# SimpleTrigger.net
KiCad netlist of a schematic drawn in EAGLE
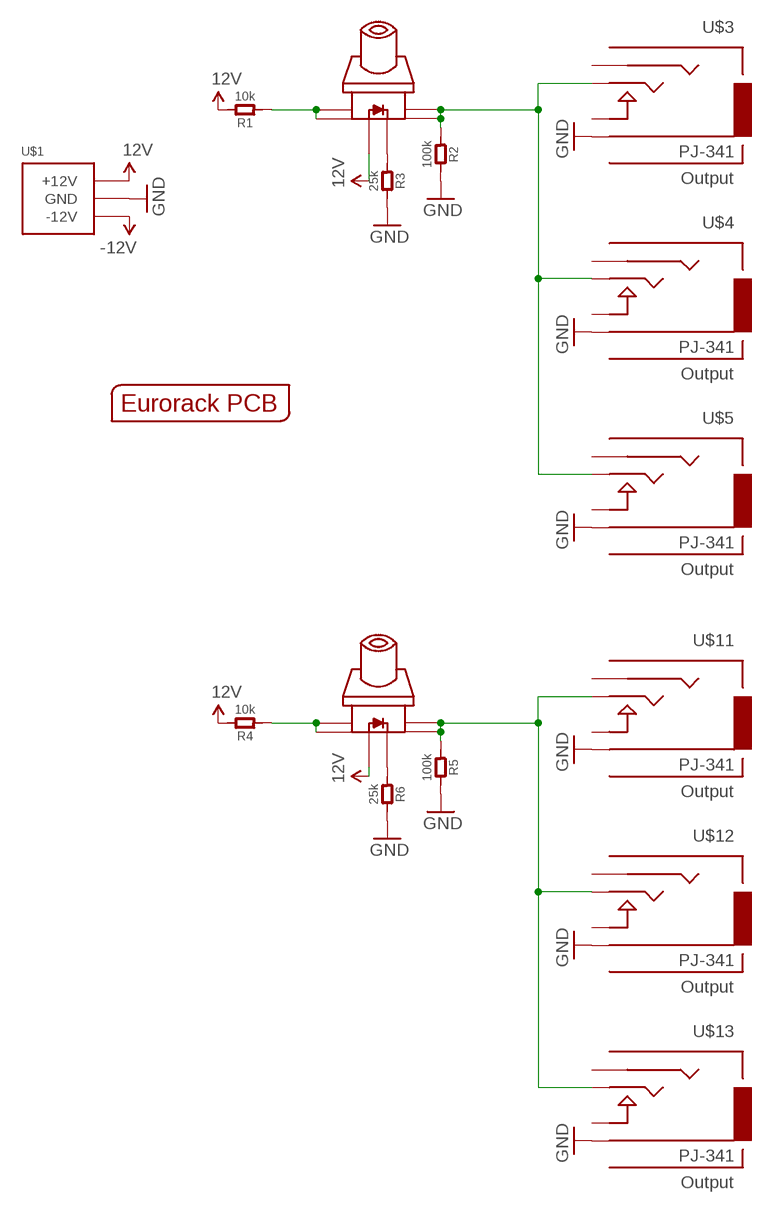
[diagram p0: schematic, sheet 1]

(export (version "E")
  (design (tool "Eeschema 10.0.6"))
  (components
    (comp (ref "R1")
      (value "10k")
      (footprint "eagle-import:R0603")
      (libsource (lib "eagle-import") (part "R-0603"))
    )
    (comp (ref "R2")
      (value "100k")
      (footprint "eagle-import:R0603")
      (libsource (lib "eagle-import") (part "R-0603"))
    )
    (comp (ref "R3")
      (value "25k")
      (footprint "eagle-import:R0603")
      (libsource (lib "eagle-import") (part "R-0603"))
    )
    (comp (ref "R4")
      (value "10k")
      (footprint "eagle-import:R0603")
      (libsource (lib "eagle-import") (part "R-0603"))
    )
    (comp (ref "R5")
      (value "100k")
      (footprint "eagle-import:R0603")
      (libsource (lib "eagle-import") (part "R-0603"))
    )
    (comp (ref "R6")
      (value "25k")
      (footprint "eagle-import:R0603")
      (libsource (lib "eagle-import") (part "R-0603"))
    )
    (comp (ref "U$1")
      (value "POWER_SIMPLE10")
      (footprint "eagle-import:POWER_10")
      (libsource (lib "eagle-import") (part "POWER_SIMPLE10"))
    )
    (comp (ref "U$2")
      (value "SWITCH_W_LED_PB6149L-X-102WHITE")
      (footprint "eagle-import:PB6149L")
      (libsource (lib "eagle-import") (part "SWITCH_W_LED_PB6149L-X-102WHITE"))
    )
    (comp (ref "U$3")
      (value "PJ-341")
      (footprint "eagle-import:3.5MM-JACK-SWITCH-13MM-OUTPUT")
      (libsource (lib "eagle-import") (part "AUDIO-JACKOUTPUT"))
    )
    (comp (ref "U$4")
      (value "PJ-341")
      (footprint "eagle-import:3.5MM-JACK-SWITCH-13MM-OUTPUT")
      (libsource (lib "eagle-import") (part "AUDIO-JACKOUTPUT"))
    )
    (comp (ref "U$5")
      (value "PJ-341")
      (footprint "eagle-import:3.5MM-JACK-SWITCH-13MM-OUTPUT")
      (libsource (lib "eagle-import") (part "AUDIO-JACKOUTPUT"))
    )
    (comp (ref "U$9")
      (value "EURORACK_PCB2HP")
      (footprint "eagle-import:EURORACK2HPPCB")
      (libsource (lib "eagle-import") (part "EURORACK_PCB2HP"))
    )
    (comp (ref "U$10")
      (value "SWITCH_W_LED_PB6149L-X-102WHITE")
      (footprint "eagle-import:PB6149L")
      (libsource (lib "eagle-import") (part "SWITCH_W_LED_PB6149L-X-102WHITE"))
    )
    (comp (ref "U$11")
      (value "PJ-341")
      (footprint "eagle-import:3.5MM-JACK-SWITCH-13MM-OUTPUT")
      (libsource (lib "eagle-import") (part "AUDIO-JACKOUTPUT"))
    )
    (comp (ref "U$12")
      (value "PJ-341")
      (footprint "eagle-import:3.5MM-JACK-SWITCH-13MM-OUTPUT")
      (libsource (lib "eagle-import") (part "AUDIO-JACKOUTPUT"))
    )
    (comp (ref "U$13")
      (value "PJ-341")
      (footprint "eagle-import:3.5MM-JACK-SWITCH-13MM-OUTPUT")
      (libsource (lib "eagle-import") (part "AUDIO-JACKOUTPUT"))
    )
  )
  (nets
    (net (code "1") (name "-12V") (class "Default")
      (node (ref "U$1") (pin "1") (pinfunction "-12V_1") (pintype "bidirectional"))
      (node (ref "U$1") (pin "2") (pinfunction "-12V_2") (pintype "bidirectional"))
    )
    (net (code "2") (name "12V") (class "Default")
      (node (ref "R1") (pin "2") (pinfunction "2_2") (pintype "bidirectional"))
      (node (ref "R4") (pin "2") (pinfunction "2_2") (pintype "bidirectional"))
      (node (ref "U$1") (pin "10") (pinfunction "+12V_10") (pintype "bidirectional"))
      (node (ref "U$1") (pin "9") (pinfunction "+12V_9") (pintype "bidirectional"))
      (node (ref "U$10") (pin "LEDPOS") (pinfunction "POS_LEDPOS") (pintype "bidirectional"))
      (node (ref "U$2") (pin "LEDPOS") (pinfunction "POS_LEDPOS") (pintype "bidirectional"))
    )
    (net (code "3") (name "GND") (class "Default")
      (node (ref "R2") (pin "2") (pinfunction "2_2") (pintype "bidirectional"))
      (node (ref "R3") (pin "2") (pinfunction "2_2") (pintype "bidirectional"))
      (node (ref "R5") (pin "2") (pinfunction "2_2") (pintype "bidirectional"))
      (node (ref "R6") (pin "2") (pinfunction "2_2") (pintype "bidirectional"))
      (node (ref "U$1") (pin "3") (pinfunction "GND_3") (pintype "bidirectional"))
      (node (ref "U$1") (pin "4") (pinfunction "GND_4") (pintype "bidirectional"))
      (node (ref "U$1") (pin "5") (pinfunction "GND_5") (pintype "bidirectional"))
      (node (ref "U$1") (pin "6") (pinfunction "GND_6") (pintype "bidirectional"))
      (node (ref "U$1") (pin "7") (pinfunction "GND_7") (pintype "bidirectional"))
      (node (ref "U$1") (pin "8") (pinfunction "GND_8") (pintype "bidirectional"))
      (node (ref "U$11") (pin "RING@3") (pinfunction "RING_RING@3") (pintype "bidirectional"))
      (node (ref "U$12") (pin "RING@3") (pinfunction "RING_RING@3") (pintype "bidirectional"))
      (node (ref "U$13") (pin "RING@3") (pinfunction "RING_RING@3") (pintype "bidirectional"))
      (node (ref "U$3") (pin "RING@3") (pinfunction "RING_RING@3") (pintype "bidirectional"))
      (node (ref "U$4") (pin "RING@3") (pinfunction "RING_RING@3") (pintype "bidirectional"))
      (node (ref "U$5") (pin "RING@3") (pinfunction "RING_RING@3") (pintype "bidirectional"))
    )
    (net (code "4") (name "Net-(R1-Pad1)") (class "Default")
      (node (ref "R1") (pin "1") (pinfunction "1_1") (pintype "bidirectional"))
      (node (ref "U$2") (pin "1") (pinfunction "1_1") (pintype "bidirectional"))
      (node (ref "U$2") (pin "2") (pinfunction "2_2") (pintype "bidirectional"))
    )
    (net (code "5") (name "Net-(R4-Pad1)") (class "Default")
      (node (ref "R4") (pin "1") (pinfunction "1_1") (pintype "bidirectional"))
      (node (ref "U$10") (pin "1") (pinfunction "1_1") (pintype "bidirectional"))
      (node (ref "U$10") (pin "2") (pinfunction "2_2") (pintype "bidirectional"))
    )
    (net (code "6") (name "Net-(U$2-NEG)") (class "Default")
      (node (ref "R3") (pin "1") (pinfunction "1_1") (pintype "bidirectional"))
      (node (ref "U$2") (pin "LEDNEG") (pinfunction "NEG_LEDNEG") (pintype "bidirectional"))
    )
    (net (code "7") (name "Net-(U$3-TIP)") (class "Default")
      (node (ref "R2") (pin "1") (pinfunction "1_1") (pintype "bidirectional"))
      (node (ref "U$2") (pin "3") (pinfunction "3_3") (pintype "bidirectional"))
      (node (ref "U$2") (pin "4") (pinfunction "4_4") (pintype "bidirectional"))
      (node (ref "U$3") (pin "TIP@3") (pinfunction "TIP_TIP@3") (pintype "bidirectional"))
      (node (ref "U$4") (pin "TIP@3") (pinfunction "TIP_TIP@3") (pintype "bidirectional"))
      (node (ref "U$5") (pin "TIP@3") (pinfunction "TIP_TIP@3") (pintype "bidirectional"))
    )
    (net (code "8") (name "Net-(U$10-NEG)") (class "Default")
      (node (ref "R6") (pin "1") (pinfunction "1_1") (pintype "bidirectional"))
      (node (ref "U$10") (pin "LEDNEG") (pinfunction "NEG_LEDNEG") (pintype "bidirectional"))
    )
    (net (code "9") (name "Net-(U$11-TIP)") (class "Default")
      (node (ref "R5") (pin "1") (pinfunction "1_1") (pintype "bidirectional"))
      (node (ref "U$10") (pin "3") (pinfunction "3_3") (pintype "bidirectional"))
      (node (ref "U$10") (pin "4") (pinfunction "4_4") (pintype "bidirectional"))
      (node (ref "U$11") (pin "TIP@3") (pinfunction "TIP_TIP@3") (pintype "bidirectional"))
      (node (ref "U$12") (pin "TIP@3") (pinfunction "TIP_TIP@3") (pintype "bidirectional"))
      (node (ref "U$13") (pin "TIP@3") (pinfunction "TIP_TIP@3") (pintype "bidirectional"))
    )
    (net (code "10") (name "unconnected-(U$3-SECOND-PadSECOND@3)") (class "Default")
      (node (ref "U$3") (pin "SECOND@3") (pinfunction "SECOND_SECOND@3") (pintype "bidirectional"))
    )
    (net (code "11") (name "unconnected-(U$3-SWITCH-PadSWITCH@3)") (class "Default")
      (node (ref "U$3") (pin "SWITCH@3") (pinfunction "SWITCH_SWITCH@3") (pintype "bidirectional"))
    )
    (net (code "12") (name "unconnected-(U$4-SECOND-PadSECOND@3)") (class "Default")
      (node (ref "U$4") (pin "SECOND@3") (pinfunction "SECOND_SECOND@3") (pintype "bidirectional"))
    )
    (net (code "13") (name "unconnected-(U$4-SWITCH-PadSWITCH@3)") (class "Default")
      (node (ref "U$4") (pin "SWITCH@3") (pinfunction "SWITCH_SWITCH@3") (pintype "bidirectional"))
    )
    (net (code "14") (name "unconnected-(U$5-SECOND-PadSECOND@3)") (class "Default")
      (node (ref "U$5") (pin "SECOND@3") (pinfunction "SECOND_SECOND@3") (pintype "bidirectional"))
    )
    (net (code "15") (name "unconnected-(U$5-SWITCH-PadSWITCH@3)") (class "Default")
      (node (ref "U$5") (pin "SWITCH@3") (pinfunction "SWITCH_SWITCH@3") (pintype "bidirectional"))
    )
    (net (code "16") (name "unconnected-(U$11-SECOND-PadSECOND@3)") (class "Default")
      (node (ref "U$11") (pin "SECOND@3") (pinfunction "SECOND_SECOND@3") (pintype "bidirectional"))
    )
    (net (code "17") (name "unconnected-(U$11-SWITCH-PadSWITCH@3)") (class "Default")
      (node (ref "U$11") (pin "SWITCH@3") (pinfunction "SWITCH_SWITCH@3") (pintype "bidirectional"))
    )
    (net (code "18") (name "unconnected-(U$12-SECOND-PadSECOND@3)") (class "Default")
      (node (ref "U$12") (pin "SECOND@3") (pinfunction "SECOND_SECOND@3") (pintype "bidirectional"))
    )
    (net (code "19") (name "unconnected-(U$12-SWITCH-PadSWITCH@3)") (class "Default")
      (node (ref "U$12") (pin "SWITCH@3") (pinfunction "SWITCH_SWITCH@3") (pintype "bidirectional"))
    )
    (net (code "20") (name "unconnected-(U$13-SECOND-PadSECOND@3)") (class "Default")
      (node (ref "U$13") (pin "SECOND@3") (pinfunction "SECOND_SECOND@3") (pintype "bidirectional"))
    )
    (net (code "21") (name "unconnected-(U$13-SWITCH-PadSWITCH@3)") (class "Default")
      (node (ref "U$13") (pin "SWITCH@3") (pinfunction "SWITCH_SWITCH@3") (pintype "bidirectional"))
    )
  )
)
